# V1.net
KiCad netlist of a schematic drawn in EAGLE
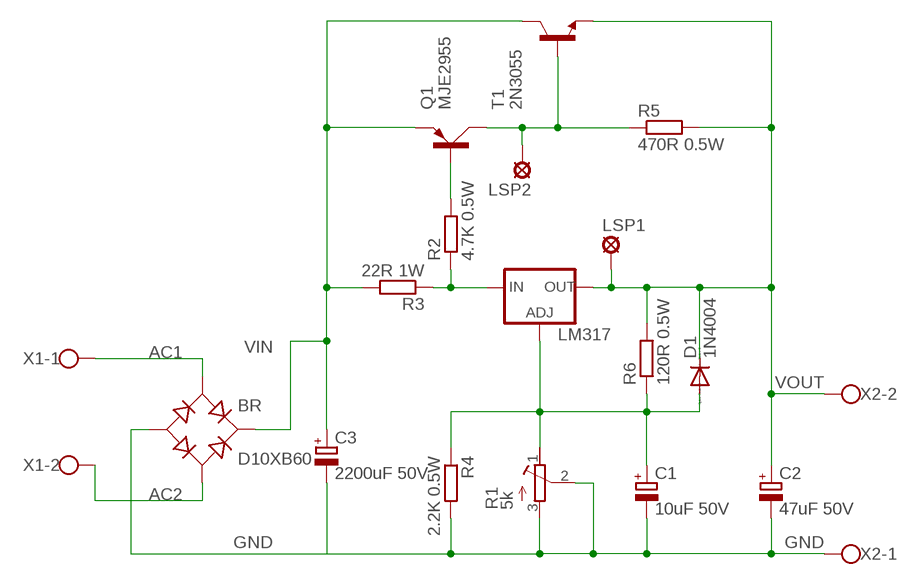
[diagram p0: schematic, sheet 1]

(export (version "E")
  (design (tool "Eeschema 10.0.6"))
  (components
    (comp (ref "BR")
      (value "D10XB60")
      (footprint "eagle-import:DX10B60")
      (libsource (lib "eagle-import") (part "D10XB60"))
    )
    (comp (ref "C1")
      (value "10uF 50V")
      (footprint "eagle-import:E2,5-5")
      (libsource (lib "eagle-import") (part "rcl_334_CPOL-EUE2.5-5"))
    )
    (comp (ref "C2")
      (value "47uF 50V")
      (footprint "eagle-import:E5-8,5")
      (libsource (lib "eagle-import") (part "CPOL-EUE5-8.5"))
    )
    (comp (ref "C3")
      (value "2200uF 50V")
      (footprint "eagle-import:E7,5-18")
      (libsource (lib "eagle-import") (part "CPOL-EUE7.5-18"))
    )
    (comp (ref "D1")
      (value "1N4004")
      (footprint "eagle-import:DO41-10")
      (libsource (lib "eagle-import") (part "1N4004"))
    )
    (comp (ref "LM317")
      (value "V_REG_317SINK")
      (footprint "eagle-import:TO220-ADJ")
      (libsource (lib "eagle-import") (part "V_REG_317SINK"))
    )
    (comp (ref "LSP1")
      (value "SE13")
      (footprint "eagle-import:SE13")
      (libsource (lib "eagle-import") (part "SE13"))
    )
    (comp (ref "LSP2")
      (value "SE13")
      (footprint "eagle-import:SE13")
      (libsource (lib "eagle-import") (part "SE13"))
    )
    (comp (ref "Q1")
      (value "MJE2955")
      (footprint "eagle-import:TO220AV")
      (libsource (lib "eagle-import") (part "MJE2955"))
    )
    (comp (ref "R1")
      (value "5k")
      (footprint "eagle-import:RTRIMT93XA")
      (libsource (lib "eagle-import") (part "R-TRIMMT93XA"))
    )
    (comp (ref "R2")
      (value "4.7K 0.5W")
      (footprint "eagle-import:0617_17")
      (libsource (lib "eagle-import") (part "R-EU_0617/17"))
    )
    (comp (ref "R3")
      (value "22R 1W")
      (footprint "eagle-import:0617_17")
      (libsource (lib "eagle-import") (part "R-EU_0617/17"))
    )
    (comp (ref "R4")
      (value "2.2K 0.5W")
      (footprint "eagle-import:0617_17")
      (libsource (lib "eagle-import") (part "R-EU_0617/17"))
    )
    (comp (ref "R5")
      (value "470R 0.5W")
      (footprint "eagle-import:0617_17")
      (libsource (lib "eagle-import") (part "R-EU_0617/17"))
    )
    (comp (ref "R6")
      (value "120R 0.5W")
      (footprint "eagle-import:0617_17")
      (libsource (lib "eagle-import") (part "R-EU_0617/17"))
    )
    (comp (ref "T1")
      (value "2N3055")
      (footprint "eagle-import:TO3")
      (libsource (lib "eagle-import") (part "2N3055"))
    )
    (comp (ref "X1")
      (value "W237-102")
      (footprint "eagle-import:W237-102")
      (fields (field (name "MPN") "237-102"))
      (libsource (lib "eagle-import") (part "W237-102"))
    )
    (comp (ref "X2")
      (value "W237-102")
      (footprint "eagle-import:W237-102")
      (fields (field (name "MPN") "237-102"))
      (libsource (lib "eagle-import") (part "W237-102"))
    )
  )
  (nets
    (net (code "1") (name "/AC1") (class "Default")
      (node (ref "BR") (pin "AC1") (pinfunction "AC1_AC1") (pintype "bidirectional"))
      (node (ref "X1") (pin "1") (pinfunction "KL_1") (pintype "passive"))
    )
    (net (code "2") (name "/AC2") (class "Default")
      (node (ref "BR") (pin "AC2") (pinfunction "AC2_AC2") (pintype "bidirectional"))
      (node (ref "X1") (pin "2") (pinfunction "KL_2") (pintype "passive"))
    )
    (net (code "3") (name "/GND") (class "Default")
      (node (ref "BR") (pin "-") (pinfunction "-_-") (pintype "bidirectional"))
      (node (ref "C1") (pin "-") (pinfunction "-_-") (pintype "passive"))
      (node (ref "C2") (pin "-") (pinfunction "-_-") (pintype "passive"))
      (node (ref "C3") (pin "-") (pinfunction "-_-") (pintype "passive"))
      (node (ref "R1") (pin "2") (pinfunction "S_2") (pintype "passive"))
      (node (ref "R1") (pin "3") (pinfunction "A_3") (pintype "passive"))
      (node (ref "R4") (pin "2") (pinfunction "2_2") (pintype "passive"))
      (node (ref "X2") (pin "1") (pinfunction "KL_1") (pintype "passive"))
    )
    (net (code "4") (name "/VIN") (class "Default")
      (node (ref "BR") (pin "+") (pinfunction "+_+") (pintype "bidirectional"))
      (node (ref "C3") (pin "+") (pinfunction "+_+") (pintype "passive"))
      (node (ref "Q1") (pin "E") (pinfunction "E_E") (pintype "passive"))
      (node (ref "R3") (pin "2") (pinfunction "2_2") (pintype "passive"))
      (node (ref "T1") (pin "C") (pinfunction "C_C") (pintype "passive"))
      (node (ref "T1") (pin "C/") (pinfunction "C_C/") (pintype "passive"))
    )
    (net (code "5") (name "/VOUT") (class "Default")
      (node (ref "C2") (pin "+") (pinfunction "+_+") (pintype "passive"))
      (node (ref "D1") (pin "C") (pinfunction "C_C") (pintype "passive"))
      (node (ref "LM317") (pin "OUT") (pinfunction "OUT_OUT") (pintype "output"))
      (node (ref "LSP1") (pin "MP") (pinfunction "MP_MP") (pintype "passive"))
      (node (ref "R5") (pin "2") (pinfunction "2_2") (pintype "passive"))
      (node (ref "R6") (pin "2") (pinfunction "2_2") (pintype "passive"))
      (node (ref "T1") (pin "E") (pinfunction "E_E") (pintype "passive"))
      (node (ref "X2") (pin "2") (pinfunction "KL_2") (pintype "passive"))
    )
    (net (code "6") (name "Net-(LM317-PadIN)") (class "Default")
      (node (ref "LM317") (pin "IN") (pinfunction "IN_IN") (pintype "input"))
      (node (ref "R2") (pin "1") (pinfunction "1_1") (pintype "passive"))
      (node (ref "R3") (pin "1") (pinfunction "1_1") (pintype "passive"))
    )
    (net (code "7") (name "Net-(LSP2-PadMP)") (class "Default")
      (node (ref "LSP2") (pin "MP") (pinfunction "MP_MP") (pintype "passive"))
      (node (ref "Q1") (pin "C") (pinfunction "C_C") (pintype "passive"))
      (node (ref "R5") (pin "1") (pinfunction "1_1") (pintype "passive"))
      (node (ref "T1") (pin "B") (pinfunction "B_B") (pintype "passive"))
    )
    (net (code "8") (name "Net-(Q1-PadB)") (class "Default")
      (node (ref "Q1") (pin "B") (pinfunction "B_B") (pintype "passive"))
      (node (ref "R2") (pin "2") (pinfunction "2_2") (pintype "passive"))
    )
    (net (code "9") (name "Net-(R1-E)") (class "Default")
      (node (ref "C1") (pin "+") (pinfunction "+_+") (pintype "passive"))
      (node (ref "D1") (pin "A") (pinfunction "A_A") (pintype "passive"))
      (node (ref "LM317") (pin "ADJ") (pinfunction "ADJ_ADJ") (pintype "input"))
      (node (ref "R1") (pin "1") (pinfunction "E_1") (pintype "passive"))
      (node (ref "R4") (pin "1") (pinfunction "1_1") (pintype "passive"))
      (node (ref "R6") (pin "1") (pinfunction "1_1") (pintype "passive"))
    )
  )
)
